# tag-connect-tc2030_v1.net
KiCad netlist of a schematic drawn in EAGLE
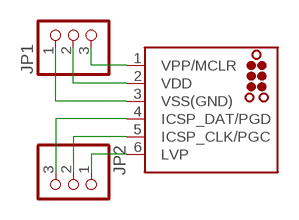
[diagram p0: schematic, sheet 1]

(export (version "E")
  (design (tool "Eeschema 10.0.6"))
  (components
    (comp (ref "JP1")
      (value "PINHD-1X3")
      (footprint "eagle-import:1X03")
      (libsource (lib "eagle-import") (part "PINHD-1X3"))
    )
    (comp (ref "JP2")
      (value "PINHD-1X3")
      (footprint "eagle-import:1X03")
      (libsource (lib "eagle-import") (part "PINHD-1X3"))
    )
    (comp (ref "TAG-CONN")
      (value "TC2030-MCP")
      (footprint "eagle-import:TC2030-MCP")
      (libsource (lib "eagle-import") (part "TC2030-MCP"))
    )
  )
  (nets
    (net (code "1") (name "Net-(TAG-CONN-ICSP_CLK{slash}PGC)") (class "Default")
      (node (ref "JP2") (pin "2") (pinfunction "2_2") (pintype "passive"))
      (node (ref "TAG-CONN") (pin "5") (pinfunction "ICSP_CLK/PGC_5") (pintype "output"))
    )
    (net (code "2") (name "Net-(TAG-CONN-ICSP_DAT{slash}PGD)") (class "Default")
      (node (ref "JP2") (pin "3") (pinfunction "3_3") (pintype "passive"))
      (node (ref "TAG-CONN") (pin "4") (pinfunction "ICSP_DAT/PGD_4") (pintype "bidirectional"))
    )
    (net (code "3") (name "Net-(TAG-CONN-LVP)") (class "Default")
      (node (ref "JP2") (pin "1") (pinfunction "1_1") (pintype "passive"))
      (node (ref "TAG-CONN") (pin "6") (pinfunction "LVP_6") (pintype "bidirectional"))
    )
    (net (code "4") (name "Net-(TAG-CONN-VDD)") (class "Default")
      (node (ref "JP1") (pin "2") (pinfunction "2_2") (pintype "passive"))
      (node (ref "TAG-CONN") (pin "2") (pinfunction "VDD_2") (pintype "power_in"))
    )
    (net (code "5") (name "Net-(TAG-CONN-VPP{slash}MCLR)") (class "Default")
      (node (ref "JP1") (pin "3") (pinfunction "3_3") (pintype "passive"))
      (node (ref "TAG-CONN") (pin "1") (pinfunction "VPP/MCLR_1") (pintype "passive"))
    )
    (net (code "6") (name "Net-(TAG-CONN-VSS(GND))") (class "Default")
      (node (ref "JP1") (pin "1") (pinfunction "1_1") (pintype "passive"))
      (node (ref "TAG-CONN") (pin "3") (pinfunction "VSS(GND)_3") (pintype "power_in"))
    )
  )
)
